# main_v1.net
KiCad netlist of a schematic drawn in EAGLE
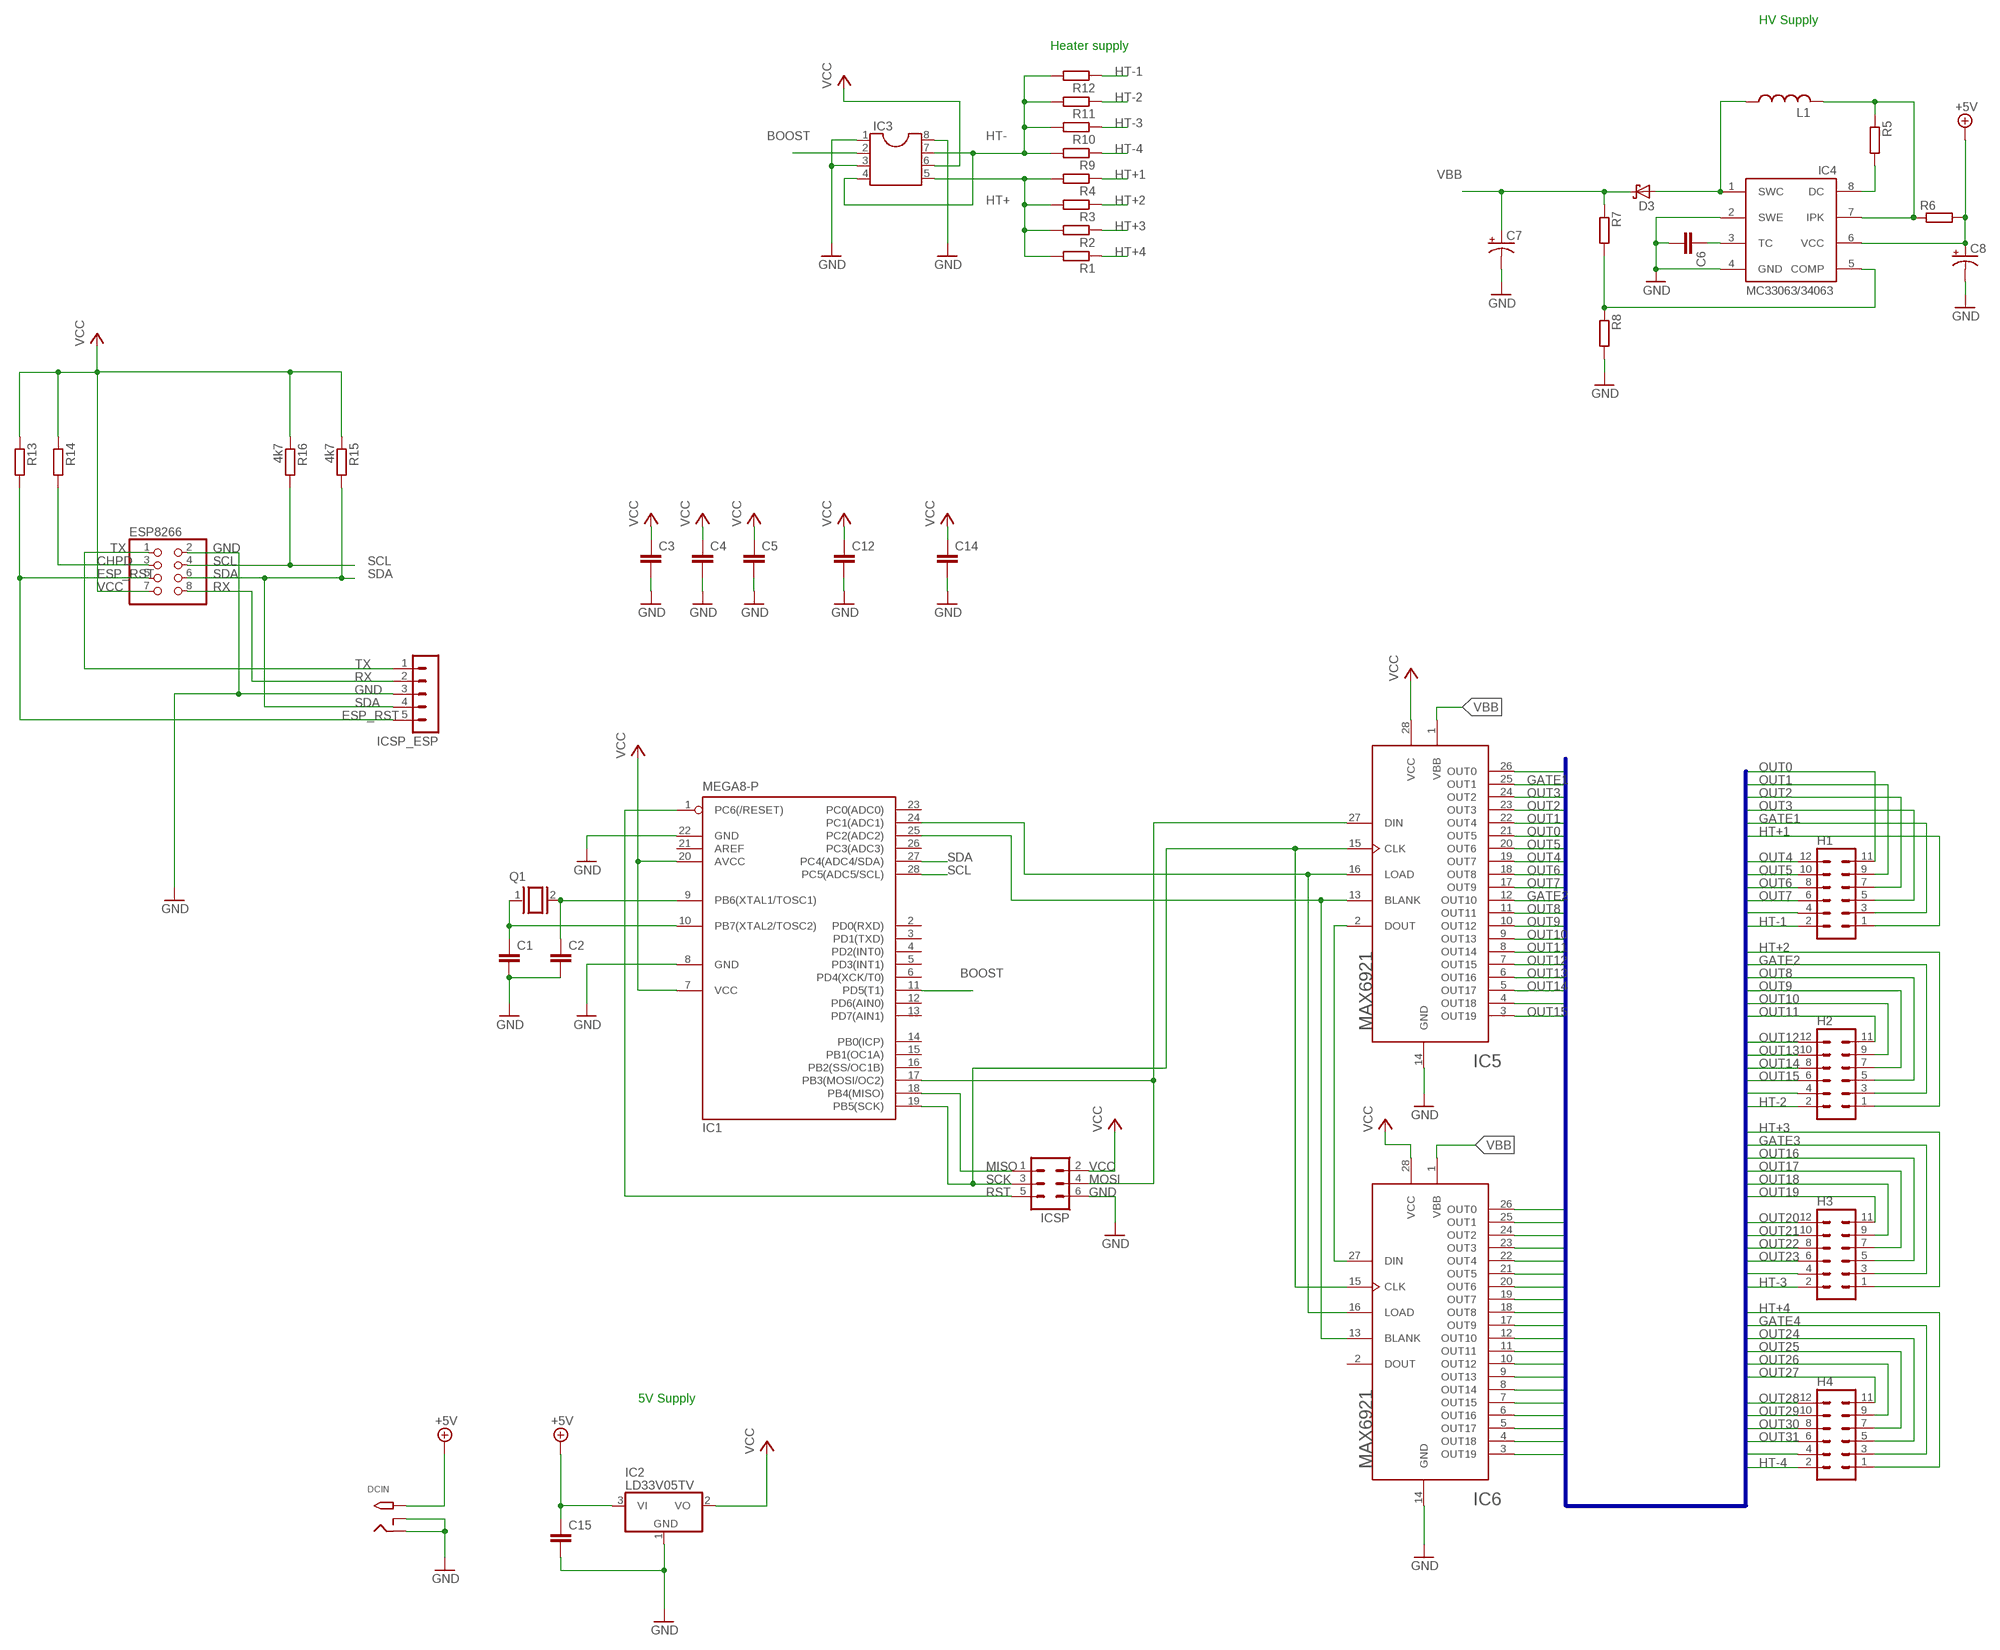
[diagram p0: schematic, sheet 1]

(export (version "E")
  (design (tool "Eeschema 10.0.6"))
  (components
    (comp (ref "C1")
      (value "C2.5/2")
      (footprint "eagle-import:C2.5-2")
      (libsource (lib "eagle-import") (part "C2.5/2"))
    )
    (comp (ref "C2")
      (value "C2.5/2")
      (footprint "eagle-import:C2.5-2")
      (libsource (lib "eagle-import") (part "C2.5/2"))
    )
    (comp (ref "C3")
      (value "C-EU025-025X050")
      (footprint "eagle-import:C025-025X050")
      (libsource (lib "eagle-import") (part "C-EU025-025X050"))
    )
    (comp (ref "C4")
      (value "C-EU025-025X050")
      (footprint "eagle-import:C025-025X050")
      (libsource (lib "eagle-import") (part "C-EU025-025X050"))
    )
    (comp (ref "C5")
      (value "C-EU025-025X050")
      (footprint "eagle-import:C025-025X050")
      (libsource (lib "eagle-import") (part "C-EU025-025X050"))
    )
    (comp (ref "C6")
      (value "C-EU025-025X050")
      (footprint "eagle-import:C025-025X050")
      (libsource (lib "eagle-import") (part "C-EU025-025X050"))
    )
    (comp (ref "C7")
      (value "CPOL-USE3.5-8")
      (footprint "eagle-import:E3,5-8")
      (libsource (lib "eagle-import") (part "CPOL-USE3.5-8"))
    )
    (comp (ref "C8")
      (value "CPOL-USE2.5-5")
      (footprint "eagle-import:E2,5-5")
      (libsource (lib "eagle-import") (part "CPOL-USE2.5-5"))
    )
    (comp (ref "C12")
      (value "C-EU025-025X050")
      (footprint "eagle-import:C025-025X050")
      (libsource (lib "eagle-import") (part "C-EU025-025X050"))
    )
    (comp (ref "C14")
      (value "C-EU025-025X050")
      (footprint "eagle-import:C025-025X050")
      (libsource (lib "eagle-import") (part "C-EU025-025X050"))
    )
    (comp (ref "C15")
      (value "C-EU025-025X050")
      (footprint "eagle-import:C025-025X050")
      (libsource (lib "eagle-import") (part "C-EU025-025X050"))
    )
    (comp (ref "D3")
      (value "SCHOTTKY-DIODEDO35-7")
      (footprint "eagle-import:DO35-7")
      (libsource (lib "eagle-import") (part "SCHOTTKY-DIODEDO35-7"))
    )
    (comp (ref "DCIN")
      (value "2.1MMJACKTHM")
      (footprint "eagle-import:PJ-102A")
      (libsource (lib "eagle-import") (part "2.1MMJACKTHM"))
    )
    (comp (ref "ESP8266")
      (value "PINHD-2X4")
      (footprint "eagle-import:2X04")
      (libsource (lib "eagle-import") (part "PINHD-2X4"))
    )
    (comp (ref "H1")
      (value "MA06-2")
      (footprint "eagle-import:MA06-2")
      (libsource (lib "eagle-import") (part "MA06-2"))
    )
    (comp (ref "H2")
      (value "MA06-2")
      (footprint "eagle-import:MA06-2")
      (libsource (lib "eagle-import") (part "MA06-2"))
    )
    (comp (ref "H3")
      (value "MA06-2")
      (footprint "eagle-import:MA06-2")
      (libsource (lib "eagle-import") (part "MA06-2"))
    )
    (comp (ref "H4")
      (value "MA06-2")
      (footprint "eagle-import:MA06-2")
      (libsource (lib "eagle-import") (part "MA06-2"))
    )
    (comp (ref "IC1")
      (value "MEGA8-P")
      (footprint "eagle-import:DIL28-3")
      (libsource (lib "eagle-import") (part "MEGA8-P"))
    )
    (comp (ref "IC2")
      (value "LD33V05TV")
      (footprint "eagle-import:TO220V")
      (libsource (lib "eagle-import") (part "LD33VTV05"))
    )
    (comp (ref "IC3")
      (value "DIL8")
      (footprint "eagle-import:DIL08")
      (libsource (lib "eagle-import") (part "DIL8"))
    )
    (comp (ref "IC4")
      (value "MC33063/MC34063P")
      (footprint "eagle-import:DIL08")
      (libsource (lib "eagle-import") (part "MC33063/MC34063P"))
    )
    (comp (ref "IC5")
      (value "MAX6921")
      (footprint "eagle-import:PLCC-S28")
      (libsource (lib "eagle-import") (part "MAX6921"))
    )
    (comp (ref "IC6")
      (value "MAX6921")
      (footprint "eagle-import:PLCC-S28")
      (libsource (lib "eagle-import") (part "MAX6921"))
    )
    (comp (ref "ICSP")
      (value "MA03-2")
      (footprint "eagle-import:MA03-2")
      (libsource (lib "eagle-import") (part "MA03-2"))
    )
    (comp (ref "ICSP_ESP")
      (value "MA05-1")
      (footprint "eagle-import:MA05-1")
      (libsource (lib "eagle-import") (part "MA05-1"))
    )
    (comp (ref "L1")
      (value "L-US6000-XXX-RC")
      (footprint "eagle-import:6000-XXXX-RC")
      (libsource (lib "eagle-import") (part "L-US6000-XXX-RC"))
    )
    (comp (ref "Q1")
      (value "XTAL/S")
      (footprint "eagle-import:QS")
      (libsource (lib "eagle-import") (part "XTAL/S"))
    )
    (comp (ref "R1")
      (value "R-EU_0204/7")
      (footprint "eagle-import:0204_7")
      (libsource (lib "eagle-import") (part "R-EU_0204/7"))
    )
    (comp (ref "R2")
      (value "R-EU_0204/7")
      (footprint "eagle-import:0204_7")
      (libsource (lib "eagle-import") (part "R-EU_0204/7"))
    )
    (comp (ref "R3")
      (value "R-EU_0204/7")
      (footprint "eagle-import:0204_7")
      (libsource (lib "eagle-import") (part "R-EU_0204/7"))
    )
    (comp (ref "R4")
      (value "R-EU_0204/7")
      (footprint "eagle-import:0204_7")
      (libsource (lib "eagle-import") (part "R-EU_0204/7"))
    )
    (comp (ref "R5")
      (value "R-EU_0204/7")
      (footprint "eagle-import:0204_7")
      (libsource (lib "eagle-import") (part "R-EU_0204/7"))
    )
    (comp (ref "R6")
      (value "R-EU_0204/7")
      (footprint "eagle-import:0204_7")
      (libsource (lib "eagle-import") (part "R-EU_0204/7"))
    )
    (comp (ref "R7")
      (value "R-EU_0204/7")
      (footprint "eagle-import:0204_7")
      (libsource (lib "eagle-import") (part "R-EU_0204/7"))
    )
    (comp (ref "R8")
      (value "R-EU_0204/7")
      (footprint "eagle-import:0204_7")
      (libsource (lib "eagle-import") (part "R-EU_0204/7"))
    )
    (comp (ref "R9")
      (value "R-EU_0204/7")
      (footprint "eagle-import:0204_7")
      (libsource (lib "eagle-import") (part "R-EU_0204/7"))
    )
    (comp (ref "R10")
      (value "R-EU_0204/7")
      (footprint "eagle-import:0204_7")
      (libsource (lib "eagle-import") (part "R-EU_0204/7"))
    )
    (comp (ref "R11")
      (value "R-EU_0204/7")
      (footprint "eagle-import:0204_7")
      (libsource (lib "eagle-import") (part "R-EU_0204/7"))
    )
    (comp (ref "R12")
      (value "R-EU_0204/7")
      (footprint "eagle-import:0204_7")
      (libsource (lib "eagle-import") (part "R-EU_0204/7"))
    )
    (comp (ref "R13")
      (value "R-EU_0207/10")
      (footprint "eagle-import:0207_10")
      (libsource (lib "eagle-import") (part "R-EU_0207/10"))
    )
    (comp (ref "R14")
      (value "R-EU_0204/7")
      (footprint "eagle-import:0204_7")
      (libsource (lib "eagle-import") (part "R-EU_0204/7"))
    )
    (comp (ref "R15")
      (value "4k7")
      (footprint "eagle-import:0204_7")
      (libsource (lib "eagle-import") (part "R-EU_0204/7"))
    )
    (comp (ref "R16")
      (value "4k7")
      (footprint "eagle-import:0204_7")
      (libsource (lib "eagle-import") (part "R-EU_0204/7"))
    )
  )
  (nets
    (net (code "1") (name "+5V") (class "Default")
      (node (ref "C15") (pin "1") (pinfunction "1_1") (pintype "passive"))
      (node (ref "C8") (pin "+") (pinfunction "+_+") (pintype "passive"))
      (node (ref "DCIN") (pin "TIP") (pinfunction "TIP_TIP") (pintype "bidirectional"))
      (node (ref "IC2") (pin "3") (pinfunction "VI_3") (pintype "input"))
      (node (ref "IC4") (pin "6") (pinfunction "VCC_6") (pintype "power_in"))
      (node (ref "R6") (pin "2") (pinfunction "2_2") (pintype "passive"))
    )
    (net (code "2") (name "/BOOST") (class "Default")
      (node (ref "IC1") (pin "11") (pinfunction "PD5(T1)_11") (pintype "bidirectional"))
      (node (ref "IC3") (pin "2") (pinfunction "2_2") (pintype "passive"))
    )
    (net (code "3") (name "/CHPD") (class "Default")
      (node (ref "ESP8266") (pin "3") (pinfunction "3_3") (pintype "passive"))
      (node (ref "R14") (pin "2") (pinfunction "2_2") (pintype "passive"))
    )
    (net (code "4") (name "/ESP_RST") (class "Default")
      (node (ref "ESP8266") (pin "5") (pinfunction "5_5") (pintype "passive"))
      (node (ref "ICSP_ESP") (pin "5") (pinfunction "5_5") (pintype "passive"))
      (node (ref "R13") (pin "2") (pinfunction "2_2") (pintype "passive"))
    )
    (net (code "5") (name "/GATE1") (class "Default")
      (node (ref "H1") (pin "3") (pinfunction "3_3") (pintype "passive"))
      (node (ref "IC5") (pin "25") (pinfunction "OUT1_25") (pintype "output"))
    )
    (net (code "6") (name "/GATE2") (class "Default")
      (node (ref "H2") (pin "3") (pinfunction "3_3") (pintype "passive"))
      (node (ref "IC5") (pin "12") (pinfunction "OUT10_12") (pintype "output"))
    )
    (net (code "7") (name "/GATE3") (class "Default")
      (node (ref "H3") (pin "3") (pinfunction "3_3") (pintype "passive"))
      (node (ref "IC6") (pin "25") (pinfunction "OUT1_25") (pintype "output"))
    )
    (net (code "8") (name "/GATE4") (class "Default")
      (node (ref "H4") (pin "3") (pinfunction "3_3") (pintype "passive"))
      (node (ref "IC6") (pin "12") (pinfunction "OUT10_12") (pintype "output"))
    )
    (net (code "9") (name "/HT+") (class "Default")
      (node (ref "IC3") (pin "5") (pinfunction "5_5") (pintype "passive"))
      (node (ref "R1") (pin "2") (pinfunction "2_2") (pintype "passive"))
      (node (ref "R2") (pin "2") (pinfunction "2_2") (pintype "passive"))
      (node (ref "R3") (pin "2") (pinfunction "2_2") (pintype "passive"))
      (node (ref "R4") (pin "2") (pinfunction "2_2") (pintype "passive"))
    )
    (net (code "10") (name "/HT+1") (class "Default")
      (node (ref "H1") (pin "1") (pinfunction "1_1") (pintype "passive"))
      (node (ref "R4") (pin "1") (pinfunction "1_1") (pintype "passive"))
    )
    (net (code "11") (name "/HT+2") (class "Default")
      (node (ref "H2") (pin "1") (pinfunction "1_1") (pintype "passive"))
      (node (ref "R3") (pin "1") (pinfunction "1_1") (pintype "passive"))
    )
    (net (code "12") (name "/HT+3") (class "Default")
      (node (ref "H3") (pin "1") (pinfunction "1_1") (pintype "passive"))
      (node (ref "R2") (pin "1") (pinfunction "1_1") (pintype "passive"))
    )
    (net (code "13") (name "/HT+4") (class "Default")
      (node (ref "H4") (pin "1") (pinfunction "1_1") (pintype "passive"))
      (node (ref "R1") (pin "1") (pinfunction "1_1") (pintype "passive"))
    )
    (net (code "14") (name "/HT-") (class "Default")
      (node (ref "IC3") (pin "4") (pinfunction "4_4") (pintype "passive"))
      (node (ref "IC3") (pin "7") (pinfunction "7_7") (pintype "passive"))
      (node (ref "R10") (pin "2") (pinfunction "2_2") (pintype "passive"))
      (node (ref "R11") (pin "2") (pinfunction "2_2") (pintype "passive"))
      (node (ref "R12") (pin "2") (pinfunction "2_2") (pintype "passive"))
      (node (ref "R9") (pin "2") (pinfunction "2_2") (pintype "passive"))
    )
    (net (code "15") (name "/HT-1") (class "Default")
      (node (ref "H1") (pin "2") (pinfunction "2_2") (pintype "passive"))
      (node (ref "R12") (pin "1") (pinfunction "1_1") (pintype "passive"))
    )
    (net (code "16") (name "/HT-2") (class "Default")
      (node (ref "H2") (pin "2") (pinfunction "2_2") (pintype "passive"))
      (node (ref "R11") (pin "1") (pinfunction "1_1") (pintype "passive"))
    )
    (net (code "17") (name "/HT-3") (class "Default")
      (node (ref "H3") (pin "2") (pinfunction "2_2") (pintype "passive"))
      (node (ref "R10") (pin "1") (pinfunction "1_1") (pintype "passive"))
    )
    (net (code "18") (name "/HT-4") (class "Default")
      (node (ref "H4") (pin "2") (pinfunction "2_2") (pintype "passive"))
      (node (ref "R9") (pin "1") (pinfunction "1_1") (pintype "passive"))
    )
    (net (code "19") (name "/MISO") (class "Default")
      (node (ref "IC1") (pin "18") (pinfunction "PB4(MISO)_18") (pintype "bidirectional"))
      (node (ref "ICSP") (pin "1") (pinfunction "1_1") (pintype "passive"))
    )
    (net (code "20") (name "/MOSI") (class "Default")
      (node (ref "IC1") (pin "17") (pinfunction "PB3(MOSI/OC2)_17") (pintype "bidirectional"))
      (node (ref "IC5") (pin "27") (pinfunction "DIN_27") (pintype "input"))
      (node (ref "ICSP") (pin "4") (pinfunction "4_4") (pintype "passive"))
    )
    (net (code "21") (name "/OUT0") (class "Default")
      (node (ref "H1") (pin "11") (pinfunction "11_11") (pintype "passive"))
      (node (ref "IC5") (pin "21") (pinfunction "OUT5_21") (pintype "output"))
    )
    (net (code "22") (name "/OUT1") (class "Default")
      (node (ref "H1") (pin "9") (pinfunction "9_9") (pintype "passive"))
      (node (ref "IC5") (pin "22") (pinfunction "OUT4_22") (pintype "output"))
    )
    (net (code "23") (name "/OUT2") (class "Default")
      (node (ref "H1") (pin "7") (pinfunction "7_7") (pintype "passive"))
      (node (ref "IC5") (pin "23") (pinfunction "OUT3_23") (pintype "output"))
    )
    (net (code "24") (name "/OUT3") (class "Default")
      (node (ref "H1") (pin "5") (pinfunction "5_5") (pintype "passive"))
      (node (ref "IC5") (pin "24") (pinfunction "OUT2_24") (pintype "output"))
    )
    (net (code "25") (name "/OUT4") (class "Default")
      (node (ref "H1") (pin "12") (pinfunction "12_12") (pintype "passive"))
      (node (ref "IC5") (pin "19") (pinfunction "OUT7_19") (pintype "output"))
    )
    (net (code "26") (name "/OUT5") (class "Default")
      (node (ref "H1") (pin "10") (pinfunction "10_10") (pintype "passive"))
      (node (ref "IC5") (pin "20") (pinfunction "OUT6_20") (pintype "output"))
    )
    (net (code "27") (name "/OUT6") (class "Default")
      (node (ref "H1") (pin "8") (pinfunction "8_8") (pintype "passive"))
      (node (ref "IC5") (pin "18") (pinfunction "OUT8_18") (pintype "output"))
    )
    (net (code "28") (name "/OUT7") (class "Default")
      (node (ref "H1") (pin "6") (pinfunction "6_6") (pintype "passive"))
      (node (ref "IC5") (pin "17") (pinfunction "OUT9_17") (pintype "output"))
    )
    (net (code "29") (name "/OUT8") (class "Default")
      (node (ref "H2") (pin "5") (pinfunction "5_5") (pintype "passive"))
      (node (ref "IC5") (pin "11") (pinfunction "OUT11_11") (pintype "output"))
    )
    (net (code "30") (name "/OUT9") (class "Default")
      (node (ref "H2") (pin "7") (pinfunction "7_7") (pintype "passive"))
      (node (ref "IC5") (pin "10") (pinfunction "OUT12_10") (pintype "output"))
    )
    (net (code "31") (name "/OUT10") (class "Default")
      (node (ref "H2") (pin "9") (pinfunction "9_9") (pintype "passive"))
      (node (ref "IC5") (pin "9") (pinfunction "OUT13_9") (pintype "output"))
    )
    (net (code "32") (name "/OUT11") (class "Default")
      (node (ref "H2") (pin "11") (pinfunction "11_11") (pintype "passive"))
      (node (ref "IC5") (pin "8") (pinfunction "OUT14_8") (pintype "output"))
    )
    (net (code "33") (name "/OUT12") (class "Default")
      (node (ref "H2") (pin "12") (pinfunction "12_12") (pintype "passive"))
      (node (ref "IC5") (pin "7") (pinfunction "OUT15_7") (pintype "output"))
    )
    (net (code "34") (name "/OUT13") (class "Default")
      (node (ref "H2") (pin "10") (pinfunction "10_10") (pintype "passive"))
      (node (ref "IC5") (pin "6") (pinfunction "OUT16_6") (pintype "output"))
    )
    (net (code "35") (name "/OUT14") (class "Default")
      (node (ref "H2") (pin "8") (pinfunction "8_8") (pintype "passive"))
      (node (ref "IC5") (pin "5") (pinfunction "OUT17_5") (pintype "output"))
    )
    (net (code "36") (name "/OUT15") (class "Default")
      (node (ref "H2") (pin "6") (pinfunction "6_6") (pintype "passive"))
      (node (ref "IC5") (pin "3") (pinfunction "OUT19_3") (pintype "output"))
    )
    (net (code "37") (name "/OUT16") (class "Default")
      (node (ref "H3") (pin "5") (pinfunction "5_5") (pintype "passive"))
      (node (ref "IC6") (pin "24") (pinfunction "OUT2_24") (pintype "output"))
    )
    (net (code "38") (name "/OUT17") (class "Default")
      (node (ref "H3") (pin "7") (pinfunction "7_7") (pintype "passive"))
      (node (ref "IC6") (pin "23") (pinfunction "OUT3_23") (pintype "output"))
    )
    (net (code "39") (name "/OUT18") (class "Default")
      (node (ref "H3") (pin "9") (pinfunction "9_9") (pintype "passive"))
      (node (ref "IC6") (pin "22") (pinfunction "OUT4_22") (pintype "output"))
    )
    (net (code "40") (name "/OUT19") (class "Default")
      (node (ref "H3") (pin "11") (pinfunction "11_11") (pintype "passive"))
      (node (ref "IC6") (pin "21") (pinfunction "OUT5_21") (pintype "output"))
    )
    (net (code "41") (name "/OUT20") (class "Default")
      (node (ref "H3") (pin "12") (pinfunction "12_12") (pintype "passive"))
      (node (ref "IC6") (pin "19") (pinfunction "OUT7_19") (pintype "output"))
    )
    (net (code "42") (name "/OUT21") (class "Default")
      (node (ref "H3") (pin "10") (pinfunction "10_10") (pintype "passive"))
      (node (ref "IC6") (pin "20") (pinfunction "OUT6_20") (pintype "output"))
    )
    (net (code "43") (name "/OUT22") (class "Default")
      (node (ref "H3") (pin "8") (pinfunction "8_8") (pintype "passive"))
      (node (ref "IC6") (pin "18") (pinfunction "OUT8_18") (pintype "output"))
    )
    (net (code "44") (name "/OUT23") (class "Default")
      (node (ref "H3") (pin "6") (pinfunction "6_6") (pintype "passive"))
      (node (ref "IC6") (pin "17") (pinfunction "OUT9_17") (pintype "output"))
    )
    (net (code "45") (name "/OUT24") (class "Default")
      (node (ref "H4") (pin "5") (pinfunction "5_5") (pintype "passive"))
      (node (ref "IC6") (pin "11") (pinfunction "OUT11_11") (pintype "output"))
    )
    (net (code "46") (name "/OUT25") (class "Default")
      (node (ref "H4") (pin "7") (pinfunction "7_7") (pintype "passive"))
      (node (ref "IC6") (pin "10") (pinfunction "OUT12_10") (pintype "output"))
    )
    (net (code "47") (name "/OUT26") (class "Default")
      (node (ref "H4") (pin "9") (pinfunction "9_9") (pintype "passive"))
      (node (ref "IC6") (pin "9") (pinfunction "OUT13_9") (pintype "output"))
    )
    (net (code "48") (name "/OUT27") (class "Default")
      (node (ref "H4") (pin "11") (pinfunction "11_11") (pintype "passive"))
      (node (ref "IC6") (pin "8") (pinfunction "OUT14_8") (pintype "output"))
    )
    (net (code "49") (name "/OUT28") (class "Default")
      (node (ref "H4") (pin "12") (pinfunction "12_12") (pintype "passive"))
      (node (ref "IC6") (pin "7") (pinfunction "OUT15_7") (pintype "output"))
    )
    (net (code "50") (name "/OUT29") (class "Default")
      (node (ref "H4") (pin "10") (pinfunction "10_10") (pintype "passive"))
      (node (ref "IC6") (pin "6") (pinfunction "OUT16_6") (pintype "output"))
    )
    (net (code "51") (name "/OUT30") (class "Default")
      (node (ref "H4") (pin "8") (pinfunction "8_8") (pintype "passive"))
      (node (ref "IC6") (pin "5") (pinfunction "OUT17_5") (pintype "output"))
    )
    (net (code "52") (name "/OUT31") (class "Default")
      (node (ref "H4") (pin "6") (pinfunction "6_6") (pintype "passive"))
      (node (ref "IC6") (pin "3") (pinfunction "OUT19_3") (pintype "output"))
    )
    (net (code "53") (name "/RST") (class "Default")
      (node (ref "IC1") (pin "1") (pinfunction "PC6(/RESET)_1") (pintype "bidirectional"))
      (node (ref "ICSP") (pin "5") (pinfunction "5_5") (pintype "passive"))
    )
    (net (code "54") (name "/RX") (class "Default")
      (node (ref "ESP8266") (pin "8") (pinfunction "8_8") (pintype "passive"))
      (node (ref "ICSP_ESP") (pin "2") (pinfunction "2_2") (pintype "passive"))
    )
    (net (code "55") (name "/SCK") (class "Default")
      (node (ref "IC1") (pin "19") (pinfunction "PB5(SCK)_19") (pintype "bidirectional"))
      (node (ref "IC5") (pin "15") (pinfunction "CLK_15") (pintype "input"))
      (node (ref "IC6") (pin "15") (pinfunction "CLK_15") (pintype "input"))
      (node (ref "ICSP") (pin "3") (pinfunction "3_3") (pintype "passive"))
    )
    (net (code "56") (name "/SCL") (class "Default")
      (node (ref "ESP8266") (pin "4") (pinfunction "4_4") (pintype "passive"))
      (node (ref "IC1") (pin "28") (pinfunction "PC5(ADC5/SCL)_28") (pintype "bidirectional"))
      (node (ref "R16") (pin "2") (pinfunction "2_2") (pintype "passive"))
    )
    (net (code "57") (name "/SDA") (class "Default")
      (node (ref "ESP8266") (pin "6") (pinfunction "6_6") (pintype "passive"))
      (node (ref "IC1") (pin "27") (pinfunction "PC4(ADC4/SDA)_27") (pintype "bidirectional"))
      (node (ref "ICSP_ESP") (pin "4") (pinfunction "4_4") (pintype "passive"))
      (node (ref "R15") (pin "2") (pinfunction "2_2") (pintype "passive"))
    )
    (net (code "58") (name "/SPARE1") (class "Default")
      (node (ref "H1") (pin "4") (pinfunction "4_4") (pintype "passive"))
      (node (ref "IC5") (pin "26") (pinfunction "OUT0_26") (pintype "output"))
    )
    (net (code "59") (name "/SPARE2") (class "Default")
      (node (ref "H2") (pin "4") (pinfunction "4_4") (pintype "passive"))
      (node (ref "IC5") (pin "4") (pinfunction "OUT18_4") (pintype "output"))
    )
    (net (code "60") (name "/SPARE3") (class "Default")
      (node (ref "H3") (pin "4") (pinfunction "4_4") (pintype "passive"))
      (node (ref "IC6") (pin "26") (pinfunction "OUT0_26") (pintype "output"))
    )
    (net (code "61") (name "/SPARE4") (class "Default")
      (node (ref "H4") (pin "4") (pinfunction "4_4") (pintype "passive"))
      (node (ref "IC6") (pin "4") (pinfunction "OUT18_4") (pintype "output"))
    )
    (net (code "62") (name "/TX") (class "Default")
      (node (ref "ESP8266") (pin "1") (pinfunction "1_1") (pintype "passive"))
      (node (ref "ICSP_ESP") (pin "1") (pinfunction "1_1") (pintype "passive"))
    )
    (net (code "63") (name "GND") (class "Default")
      (node (ref "C1") (pin "2") (pinfunction "2_2") (pintype "passive"))
      (node (ref "C12") (pin "2") (pinfunction "2_2") (pintype "passive"))
      (node (ref "C14") (pin "2") (pinfunction "2_2") (pintype "passive"))
      (node (ref "C15") (pin "2") (pinfunction "2_2") (pintype "passive"))
      (node (ref "C2") (pin "2") (pinfunction "2_2") (pintype "passive"))
      (node (ref "C3") (pin "2") (pinfunction "2_2") (pintype "passive"))
      (node (ref "C4") (pin "2") (pinfunction "2_2") (pintype "passive"))
      (node (ref "C5") (pin "2") (pinfunction "2_2") (pintype "passive"))
      (node (ref "C6") (pin "2") (pinfunction "2_2") (pintype "passive"))
      (node (ref "C7") (pin "-") (pinfunction "-_-") (pintype "passive"))
      (node (ref "C8") (pin "-") (pinfunction "-_-") (pintype "passive"))
      (node (ref "DCIN") (pin "RING") (pinfunction "RING_RING") (pintype "bidirectional"))
      (node (ref "DCIN") (pin "RING_SW") (pinfunction "RING_SW_RING_SW") (pintype "bidirectional"))
      (node (ref "ESP8266") (pin "2") (pinfunction "2_2") (pintype "passive"))
      (node (ref "IC1") (pin "22") (pinfunction "GND_22") (pintype "power_in"))
      (node (ref "IC1") (pin "8") (pinfunction "GND_8") (pintype "power_in"))
      (node (ref "IC2") (pin "1") (pinfunction "GND_1") (pintype "passive"))
      (node (ref "IC3") (pin "1") (pinfunction "1_1") (pintype "passive"))
      (node (ref "IC3") (pin "3") (pinfunction "3_3") (pintype "passive"))
      (node (ref "IC3") (pin "8") (pinfunction "8_8") (pintype "passive"))
      (node (ref "IC4") (pin "2") (pinfunction "SWE_2") (pintype "input"))
      (node (ref "IC4") (pin "4") (pinfunction "GND_4") (pintype "power_in"))
      (node (ref "IC5") (pin "14") (pinfunction "GND_14") (pintype "power_in"))
      (node (ref "IC6") (pin "14") (pinfunction "GND_14") (pintype "power_in"))
      (node (ref "ICSP") (pin "6") (pinfunction "6_6") (pintype "passive"))
      (node (ref "ICSP_ESP") (pin "3") (pinfunction "3_3") (pintype "passive"))
      (node (ref "R8") (pin "2") (pinfunction "2_2") (pintype "passive"))
    )
    (net (code "64") (name "Net-(IC1-PB6(XTAL1{slash}TOSC1))") (class "Default")
      (node (ref "C2") (pin "1") (pinfunction "1_1") (pintype "passive"))
      (node (ref "IC1") (pin "9") (pinfunction "PB6(XTAL1/TOSC1)_9") (pintype "bidirectional"))
      (node (ref "Q1") (pin "2") (pinfunction "2_2") (pintype "passive"))
    )
    (net (code "65") (name "Net-(IC1-PB7(XTAL2{slash}TOSC2))") (class "Default")
      (node (ref "C1") (pin "1") (pinfunction "1_1") (pintype "passive"))
      (node (ref "IC1") (pin "10") (pinfunction "PB7(XTAL2/TOSC2)_10") (pintype "bidirectional"))
      (node (ref "Q1") (pin "1") (pinfunction "1_1") (pintype "passive"))
    )
    (net (code "66") (name "Net-(IC1-PC1(ADC1))") (class "Default")
      (node (ref "IC1") (pin "24") (pinfunction "PC1(ADC1)_24") (pintype "bidirectional"))
      (node (ref "IC5") (pin "16") (pinfunction "LOAD_16") (pintype "input"))
      (node (ref "IC6") (pin "16") (pinfunction "LOAD_16") (pintype "input"))
    )
    (net (code "67") (name "Net-(IC1-PC2(ADC2))") (class "Default")
      (node (ref "IC1") (pin "25") (pinfunction "PC2(ADC2)_25") (pintype "bidirectional"))
      (node (ref "IC5") (pin "13") (pinfunction "BLANK_13") (pintype "input"))
      (node (ref "IC6") (pin "13") (pinfunction "BLANK_13") (pintype "input"))
    )
    (net (code "68") (name "Net-(IC4-COMP)") (class "Default")
      (node (ref "IC4") (pin "5") (pinfunction "COMP_5") (pintype "input"))
      (node (ref "R7") (pin "2") (pinfunction "2_2") (pintype "passive"))
      (node (ref "R8") (pin "1") (pinfunction "1_1") (pintype "passive"))
    )
    (net (code "69") (name "Net-(IC4-DC)") (class "Default")
      (node (ref "IC4") (pin "8") (pinfunction "DC_8") (pintype "input"))
      (node (ref "R5") (pin "2") (pinfunction "2_2") (pintype "passive"))
    )
    (net (code "70") (name "Net-(IC4-IPK)") (class "Default")
      (node (ref "IC4") (pin "7") (pinfunction "IPK_7") (pintype "bidirectional"))
      (node (ref "L1") (pin "2") (pinfunction "2_2") (pintype "passive"))
      (node (ref "R5") (pin "1") (pinfunction "1_1") (pintype "passive"))
      (node (ref "R6") (pin "1") (pinfunction "1_1") (pintype "passive"))
    )
    (net (code "71") (name "Net-(IC4-SWC)") (class "Default")
      (node (ref "D3") (pin "A") (pinfunction "A_A") (pintype "passive"))
      (node (ref "IC4") (pin "1") (pinfunction "SWC_1") (pintype "input"))
      (node (ref "L1") (pin "1") (pinfunction "1_1") (pintype "passive"))
    )
    (net (code "72") (name "Net-(IC4-TC)") (class "Default")
      (node (ref "C6") (pin "1") (pinfunction "1_1") (pintype "passive"))
      (node (ref "IC4") (pin "3") (pinfunction "TC_3") (pintype "input"))
    )
    (net (code "73") (name "Net-(IC5-DOUT)") (class "Default")
      (node (ref "IC5") (pin "2") (pinfunction "DOUT_2") (pintype "output"))
      (node (ref "IC6") (pin "27") (pinfunction "DIN_27") (pintype "input"))
    )
    (net (code "74") (name "VBB") (class "Default")
      (node (ref "C7") (pin "+") (pinfunction "+_+") (pintype "passive"))
      (node (ref "D3") (pin "C") (pinfunction "C_C") (pintype "passive"))
      (node (ref "IC5") (pin "1") (pinfunction "VBB_1") (pintype "power_in"))
      (node (ref "IC6") (pin "1") (pinfunction "VBB_1") (pintype "power_in"))
      (node (ref "R7") (pin "1") (pinfunction "1_1") (pintype "passive"))
    )
    (net (code "75") (name "VCC") (class "Default")
      (node (ref "C12") (pin "1") (pinfunction "1_1") (pintype "passive"))
      (node (ref "C14") (pin "1") (pinfunction "1_1") (pintype "passive"))
      (node (ref "C3") (pin "1") (pinfunction "1_1") (pintype "passive"))
      (node (ref "C4") (pin "1") (pinfunction "1_1") (pintype "passive"))
      (node (ref "C5") (pin "1") (pinfunction "1_1") (pintype "passive"))
      (node (ref "ESP8266") (pin "7") (pinfunction "7_7") (pintype "passive"))
      (node (ref "IC1") (pin "20") (pinfunction "AVCC_20") (pintype "power_in"))
      (node (ref "IC1") (pin "7") (pinfunction "VCC_7") (pintype "power_in"))
      (node (ref "IC2") (pin "2") (pinfunction "VO_2") (pintype "passive"))
      (node (ref "IC3") (pin "6") (pinfunction "6_6") (pintype "passive"))
      (node (ref "IC5") (pin "28") (pinfunction "VCC_28") (pintype "power_in"))
      (node (ref "IC6") (pin "28") (pinfunction "VCC_28") (pintype "power_in"))
      (node (ref "ICSP") (pin "2") (pinfunction "2_2") (pintype "passive"))
      (node (ref "R13") (pin "1") (pinfunction "1_1") (pintype "passive"))
      (node (ref "R14") (pin "1") (pinfunction "1_1") (pintype "passive"))
      (node (ref "R15") (pin "1") (pinfunction "1_1") (pintype "passive"))
      (node (ref "R16") (pin "1") (pinfunction "1_1") (pintype "passive"))
    )
    (net (code "76") (name "unconnected-(IC1-AREF-Pad21)") (class "Default")
      (node (ref "IC1") (pin "21") (pinfunction "AREF_21") (pintype "passive"))
    )
    (net (code "77") (name "unconnected-(IC1-PB0(ICP)-Pad14)") (class "Default")
      (node (ref "IC1") (pin "14") (pinfunction "PB0(ICP)_14") (pintype "bidirectional"))
    )
    (net (code "78") (name "unconnected-(IC1-PB1(OC1A)-Pad15)") (class "Default")
      (node (ref "IC1") (pin "15") (pinfunction "PB1(OC1A)_15") (pintype "bidirectional"))
    )
    (net (code "79") (name "unconnected-(IC1-PB2(SS{slash}OC1B)-Pad16)") (class "Default")
      (node (ref "IC1") (pin "16") (pinfunction "PB2(SS/OC1B)_16") (pintype "bidirectional"))
    )
    (net (code "80") (name "unconnected-(IC1-PC0(ADC0)-Pad23)") (class "Default")
      (node (ref "IC1") (pin "23") (pinfunction "PC0(ADC0)_23") (pintype "bidirectional"))
    )
    (net (code "81") (name "unconnected-(IC1-PC3(ADC3)-Pad26)") (class "Default")
      (node (ref "IC1") (pin "26") (pinfunction "PC3(ADC3)_26") (pintype "bidirectional"))
    )
    (net (code "82") (name "unconnected-(IC1-PD0(RXD)-Pad2)") (class "Default")
      (node (ref "IC1") (pin "2") (pinfunction "PD0(RXD)_2") (pintype "bidirectional"))
    )
    (net (code "83") (name "unconnected-(IC1-PD1(TXD)-Pad3)") (class "Default")
      (node (ref "IC1") (pin "3") (pinfunction "PD1(TXD)_3") (pintype "bidirectional"))
    )
    (net (code "84") (name "unconnected-(IC1-PD2(INT0)-Pad4)") (class "Default")
      (node (ref "IC1") (pin "4") (pinfunction "PD2(INT0)_4") (pintype "bidirectional"))
    )
    (net (code "85") (name "unconnected-(IC1-PD3(INT1)-Pad5)") (class "Default")
      (node (ref "IC1") (pin "5") (pinfunction "PD3(INT1)_5") (pintype "bidirectional"))
    )
    (net (code "86") (name "unconnected-(IC1-PD4(XCK{slash}T0)-Pad6)") (class "Default")
      (node (ref "IC1") (pin "6") (pinfunction "PD4(XCK/T0)_6") (pintype "bidirectional"))
    )
    (net (code "87") (name "unconnected-(IC1-PD6(AIN0)-Pad12)") (class "Default")
      (node (ref "IC1") (pin "12") (pinfunction "PD6(AIN0)_12") (pintype "bidirectional"))
    )
    (net (code "88") (name "unconnected-(IC1-PD7(AIN1)-Pad13)") (class "Default")
      (node (ref "IC1") (pin "13") (pinfunction "PD7(AIN1)_13") (pintype "bidirectional"))
    )
    (net (code "89") (name "unconnected-(IC6-DOUT-Pad2)") (class "Default")
      (node (ref "IC6") (pin "2") (pinfunction "DOUT_2") (pintype "output"))
    )
  )
)
